# Buzzer_and_Relay.net
KiCad netlist of a schematic drawn in Altium Designer
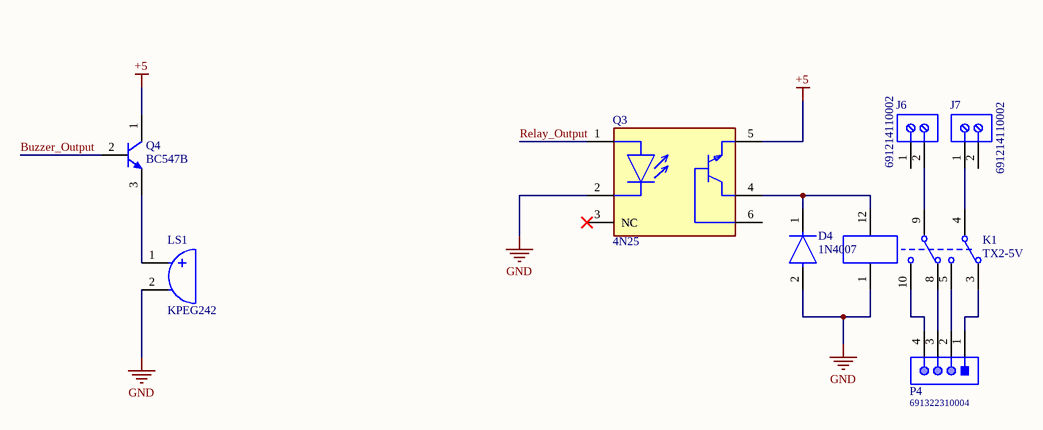
[diagram p0: Buzzer and Relay.SchDoc]

(export (version "E")
  (design (tool "Eeschema 10.0.6"))
  (components
    (comp (ref "D4")
      (value "1N4007")
      (footprint "FP-1N4007-MFG")
      (description "Rectifier diode 1000 V 1 A DO-41, ,")
      (fields
        (field (name "MANUFACTURER") "Diotec")
        (field (name "OCTOPART") "https://octopart.com/1n4007-diotec-4040411")
      )
      (libsource (lib "Altium Content Vault") (part "d7152d700b627762746794eb795d46e"))
    )
    (comp (ref "J6")
      (value "691214110002")
      (footprint "691214110002")
      (description "Serie 2141 - 3.50 mm Horizontal Entry Modular with Rising Cage Clamp WR-TBL, 2 pin")
      (fields (field (name "MANUFACTURER") "Wurth Elektronik") (field (name "PUBLISHER") "WurthElektronik"))
      (libsource (lib "Altium Content Vault") (part "WE-CN-1P-F-TB2"))
    )
    (comp (ref "J7")
      (value "691214110002")
      (footprint "691214110002")
      (description "Serie 2141 - 3.50 mm Horizontal Entry Modular with Rising Cage Clamp WR-TBL, 2 pin")
      (fields (field (name "MANUFACTURER") "Wurth Elektronik") (field (name "PUBLISHER") "WurthElektronik"))
      (libsource (lib "Altium Content Vault") (part "WE-CN-1P-F-TB2"))
    )
    (comp (ref "K1")
      (value "TX2-5V")
      (footprint "PNSC-TX2-5V_V")
      (fields
        (field (name "MANUFACTURER") "Panasonic")
        (field (name "APPROVAL CATEGORY") "EN41003")
        (field (name "APPROVAL BODIES") "CSA/UL")
      )
      (libsource (lib "Altium Content Vault") (part "PNSC-RELAY-DPDT-8"))
    )
    (comp (ref "LS1")
      (value "KPEG242")
      (footprint "KINGS-KPEG242-2")
      (description "Piezo Indicator, 4100 Hz, 3 to 16 V, -20 to 70 degC, 2-Pin THD, RoHS")
      (fields (field (name "PARTNUMBER") "KPE-242") (field (name "MANUFACTURER") "KingstateElectronicsCorp."))
      (libsource (lib "Altium Content Vault") (part "KINGS-KPEG242-2"))
    )
    (comp (ref "P4")
      (value "691322310004")
      (footprint "691322310004")
      (description "Serie 322 - 3.81mm Horizontal PCB Header WR-TBL, 4 pin")
      (fields (field (name "MANUFACTURER") "Wurth Elektronik") (field (name "PUBLISHER") "WurthElektronik"))
      (libsource (lib "Altium Content Vault") (part "WE-CN-1P-M-R4"))
    )
    (comp (ref "Q3")
      (value "4N25")
      (footprint "FP-4N25-MFG")
      (description "OPTOISO 2.5KV TRANS W/BASE 6DIP")
      (libsource (lib "Altium Content Vault") (part "f1df9f29c47de6998195431899ac75d"))
    )
    (comp (ref "Q4")
      (value "BC547B")
      (footprint "ONSC-TO-92-3-29-11")
      (description "Amplifier Transistor, NPN Silicon, 3-Pin TO-92, Bulk Box")
      (fields (field (name "MANUFACTURER") "On Semiconductor"))
      (libsource (lib "Altium Content Vault") (part "ONSC-NPN-C1B2E3-3"))
    )
  )
  (nets
    (net (code "1") (name "+5") (class "Default")
      (node (ref "Q3") (pin "5") (pinfunction "C_5") (pintype "passive"))
      (node (ref "Q4") (pin "1") (pinfunction "C_1") (pintype "passive"))
    )
    (net (code "2") (name "/Buzzer_Output") (class "Default")
      (node (ref "Q4") (pin "2") (pinfunction "B_2") (pintype "passive"))
    )
    (net (code "3") (name "/Relay_Output") (class "Default")
      (node (ref "Q3") (pin "1") (pinfunction "A_1") (pintype "passive"))
    )
    (net (code "4") (name "GND") (class "Default")
      (node (ref "D4") (pin "2") (pinfunction "A_2") (pintype "passive"))
      (node (ref "K1") (pin "1") (pinfunction "1_1") (pintype "passive"))
      (node (ref "LS1") (pin "2") (pinfunction "2_2") (pintype "passive"))
      (node (ref "Q3") (pin "2") (pinfunction "C_2") (pintype "passive"))
    )
    (net (code "5") (name "Net-(D4-C)") (class "Default")
      (node (ref "D4") (pin "1") (pinfunction "C_1") (pintype "passive"))
      (node (ref "K1") (pin "12") (pinfunction "12_12") (pintype "passive"))
      (node (ref "Q3") (pin "4") (pinfunction "E_4") (pintype "passive"))
    )
    (net (code "6") (name "Net-(J6-Pad2)") (class "Default")
      (node (ref "J6") (pin "2") (pinfunction "2_2") (pintype "passive"))
      (node (ref "K1") (pin "9") (pinfunction "9_9") (pintype "passive"))
    )
    (net (code "7") (name "Net-(J7-Pad1)") (class "Default")
      (node (ref "J7") (pin "1") (pinfunction "1_1") (pintype "passive"))
      (node (ref "K1") (pin "4") (pinfunction "4_4") (pintype "passive"))
    )
    (net (code "8") (name "Net-(K1-Pad3)") (class "Default")
      (node (ref "K1") (pin "3") (pinfunction "3_3") (pintype "passive"))
      (node (ref "P4") (pin "1") (pinfunction "1_1") (pintype "passive"))
    )
    (net (code "9") (name "Net-(K1-Pad5)") (class "Default")
      (node (ref "K1") (pin "5") (pinfunction "5_5") (pintype "passive"))
      (node (ref "P4") (pin "2") (pinfunction "2_2") (pintype "passive"))
    )
    (net (code "10") (name "Net-(K1-Pad8)") (class "Default")
      (node (ref "K1") (pin "8") (pinfunction "8_8") (pintype "passive"))
      (node (ref "P4") (pin "3") (pinfunction "3_3") (pintype "passive"))
    )
    (net (code "11") (name "Net-(K1-Pad10)") (class "Default")
      (node (ref "K1") (pin "10") (pinfunction "10_10") (pintype "passive"))
      (node (ref "P4") (pin "4") (pinfunction "4_4") (pintype "passive"))
    )
    (net (code "12") (name "Net-(Q4-E)") (class "Default")
      (node (ref "LS1") (pin "1") (pinfunction "1_1") (pintype "passive"))
      (node (ref "Q4") (pin "3") (pinfunction "E_3") (pintype "passive"))
    )
    (net (code "13") (name "unconnected-(J6-Pad1)") (class "Default")
      (node (ref "J6") (pin "1") (pinfunction "1_1") (pintype "passive"))
    )
    (net (code "14") (name "unconnected-(J7-Pad2)") (class "Default")
      (node (ref "J7") (pin "2") (pinfunction "2_2") (pintype "passive"))
    )
    (net (code "15") (name "unconnected-(Q3-B-Pad6)") (class "Default")
      (node (ref "Q3") (pin "6") (pinfunction "B_6") (pintype "passive"))
    )
    (net (code "16") (name "unconnected-(Q3-NC-Pad3)") (class "Default")
      (node (ref "Q3") (pin "3") (pinfunction "NC_3") (pintype "passive+no_connect"))
    )
  )
)
